# AD8495_x1_breakout.net
KiCad netlist of a schematic drawn in EAGLE
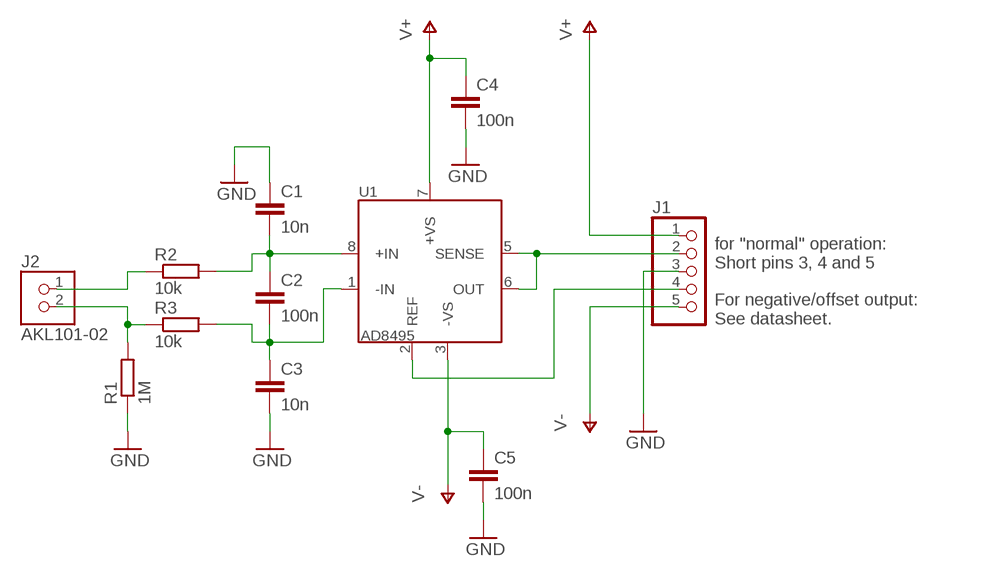
[diagram p0: schematic, sheet 1]

(export (version "E")
  (design (tool "Eeschema 10.0.6"))
  (components
    (comp (ref "C1")
      (value "10n")
      (footprint "eagle-import:C0805")
      (libsource (lib "eagle-import") (part "C-EUC0805"))
    )
    (comp (ref "C2")
      (value "100n")
      (footprint "eagle-import:C0805")
      (libsource (lib "eagle-import") (part "C-EUC0805"))
    )
    (comp (ref "C3")
      (value "10n")
      (footprint "eagle-import:C0805")
      (libsource (lib "eagle-import") (part "C-EUC0805"))
    )
    (comp (ref "C4")
      (value "100n")
      (footprint "eagle-import:C0805")
      (libsource (lib "eagle-import") (part "C-EUC0805"))
    )
    (comp (ref "C5")
      (value "100n")
      (footprint "eagle-import:C0805")
      (libsource (lib "eagle-import") (part "C-EUC0805"))
    )
    (comp (ref "J1")
      (value "PINHD-1X5")
      (footprint "eagle-import:1X05")
      (libsource (lib "eagle-import") (part "PINHD-1X5"))
    )
    (comp (ref "J2")
      (value "AKL101-02")
      (footprint "eagle-import:AKL101-02")
      (libsource (lib "eagle-import") (part "AKL101-02"))
    )
    (comp (ref "R1")
      (value "1M")
      (footprint "eagle-import:R0805")
      (libsource (lib "eagle-import") (part "R-EUR0805"))
    )
    (comp (ref "R2")
      (value "10k")
      (footprint "eagle-import:R0805")
      (libsource (lib "eagle-import") (part "R-EUR0805"))
    )
    (comp (ref "R3")
      (value "10k")
      (footprint "eagle-import:R0805")
      (libsource (lib "eagle-import") (part "R-EUR0805"))
    )
    (comp (ref "U1")
      (value "AD8495RMZ")
      (footprint "eagle-import:MS_MSOP8")
      (libsource (lib "eagle-import") (part "AD8495RMZ"))
    )
  )
  (nets
    (net (code "1") (name "GND") (class "Default")
      (node (ref "C1") (pin "1") (pinfunction "1_1") (pintype "passive"))
      (node (ref "C3") (pin "2") (pinfunction "2_2") (pintype "passive"))
      (node (ref "C4") (pin "2") (pinfunction "2_2") (pintype "passive"))
      (node (ref "C5") (pin "2") (pinfunction "2_2") (pintype "passive"))
      (node (ref "J1") (pin "3") (pinfunction "3_3") (pintype "passive"))
      (node (ref "R1") (pin "1") (pinfunction "1_1") (pintype "passive"))
    )
    (net (code "2") (name "Net-(J2-Pad1)") (class "Default")
      (node (ref "J2") (pin "1") (pinfunction "1_1") (pintype "passive"))
      (node (ref "R2") (pin "1") (pinfunction "1_1") (pintype "passive"))
    )
    (net (code "3") (name "Net-(J2-Pad2)") (class "Default")
      (node (ref "J2") (pin "2") (pinfunction "2_2") (pintype "passive"))
      (node (ref "R1") (pin "2") (pinfunction "2_2") (pintype "passive"))
      (node (ref "R3") (pin "1") (pinfunction "1_1") (pintype "passive"))
    )
    (net (code "4") (name "Net-(U1-+IN)") (class "Default")
      (node (ref "C1") (pin "2") (pinfunction "2_2") (pintype "passive"))
      (node (ref "C2") (pin "1") (pinfunction "1_1") (pintype "passive"))
      (node (ref "R2") (pin "2") (pinfunction "2_2") (pintype "passive"))
      (node (ref "U1") (pin "8") (pinfunction "+IN_8") (pintype "passive"))
    )
    (net (code "5") (name "Net-(U1--IN)") (class "Default")
      (node (ref "C2") (pin "2") (pinfunction "2_2") (pintype "passive"))
      (node (ref "C3") (pin "1") (pinfunction "1_1") (pintype "passive"))
      (node (ref "R3") (pin "2") (pinfunction "2_2") (pintype "passive"))
      (node (ref "U1") (pin "1") (pinfunction "-IN_1") (pintype "passive"))
    )
    (net (code "6") (name "Net-(U1-OUT)") (class "Default")
      (node (ref "J1") (pin "2") (pinfunction "2_2") (pintype "passive"))
      (node (ref "U1") (pin "5") (pinfunction "SENSE_5") (pintype "input"))
      (node (ref "U1") (pin "6") (pinfunction "OUT_6") (pintype "output"))
    )
    (net (code "7") (name "Net-(U1-REF)") (class "Default")
      (node (ref "J1") (pin "4") (pinfunction "4_4") (pintype "passive"))
      (node (ref "U1") (pin "2") (pinfunction "REF_2") (pintype "input"))
    )
    (net (code "8") (name "V+") (class "Default")
      (node (ref "C4") (pin "1") (pinfunction "1_1") (pintype "passive"))
      (node (ref "J1") (pin "1") (pinfunction "1_1") (pintype "passive"))
      (node (ref "U1") (pin "7") (pinfunction "+VS_7") (pintype "power_in"))
    )
    (net (code "9") (name "V-") (class "Default")
      (node (ref "C5") (pin "1") (pinfunction "1_1") (pintype "passive"))
      (node (ref "J1") (pin "5") (pinfunction "5_5") (pintype "passive"))
      (node (ref "U1") (pin "3") (pinfunction "-VS_3") (pintype "power_in"))
    )
  )
)
